# SDI_1521L_BREAKOUT_BOARD.net
KiCad netlist of a schematic drawn in Altium Designer
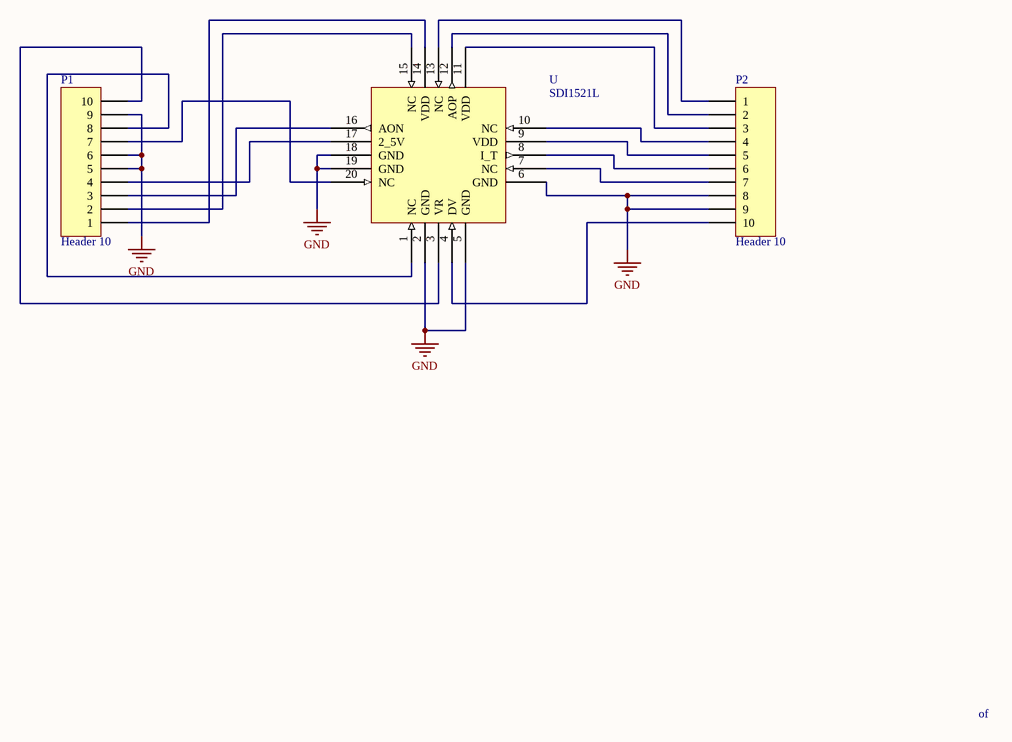
[diagram p0: SDI_1521L_BREAKOUT_BOARD.SchDoc]

(export (version "E")
  (design (tool "Eeschema 10.0.6"))
  (components
    (comp (ref "P1")
      (value "Header 10")
      (footprint "HDR1X10")
      (description "Header, 10-Pin")
      (fields (field (name "PUBLISHER") "Altium Limited"))
      (libsource (lib "") (part "Header 10_1"))
    )
    (comp (ref "P2")
      (value "Header 10")
      (footprint "HDR1X10")
      (description "Header, 10-Pin")
      (fields (field (name "PUBLISHER") "Altium Limited"))
      (libsource (lib "Miscellaneous Connectors") (part "Header 10"))
    )
    (comp (ref "U")
      (value "SDI1521L")
      (footprint "SDI 1521L")
      (description "SDI1521L Accelerometer +/- 2G")
      (libsource (lib "GAINS_SCH") (part "SDI1521L"))
    )
  )
  (nets
    (net (code "1") (name "GND") (class "Default")
      (node (ref "P1") (pin "5") (pinfunction "5_5") (pintype "passive"))
      (node (ref "P1") (pin "6") (pinfunction "6_6") (pintype "passive"))
      (node (ref "P1") (pin "9") (pinfunction "9_9") (pintype "passive"))
      (node (ref "P2") (pin "8") (pinfunction "8_8") (pintype "passive"))
      (node (ref "P2") (pin "9") (pinfunction "9_9") (pintype "passive"))
      (node (ref "U") (pin "18") (pinfunction "GND_18") (pintype "passive"))
      (node (ref "U") (pin "19") (pinfunction "GND_19") (pintype "passive"))
      (node (ref "U") (pin "2") (pinfunction "GND_2") (pintype "passive"))
      (node (ref "U") (pin "5") (pinfunction "GND_5") (pintype "passive"))
      (node (ref "U") (pin "6") (pinfunction "GND_6") (pintype "passive"))
    )
    (net (code "2") (name "Net-(P1-Pad1)") (class "Default")
      (node (ref "P1") (pin "1") (pinfunction "1_1") (pintype "passive"))
      (node (ref "U") (pin "14") (pinfunction "VDD_14") (pintype "passive"))
    )
    (net (code "3") (name "Net-(P1-Pad2)") (class "Default")
      (node (ref "P1") (pin "2") (pinfunction "2_2") (pintype "passive"))
      (node (ref "U") (pin "15") (pinfunction "NC_15") (pintype "input"))
    )
    (net (code "4") (name "Net-(P1-Pad7)") (class "Default")
      (node (ref "P1") (pin "7") (pinfunction "7_7") (pintype "passive"))
      (node (ref "U") (pin "20") (pinfunction "NC_20") (pintype "input"))
    )
    (net (code "5") (name "Net-(P1-Pad8)") (class "Default")
      (node (ref "P1") (pin "8") (pinfunction "8_8") (pintype "passive"))
      (node (ref "U") (pin "1") (pinfunction "NC_1") (pintype "input"))
    )
    (net (code "6") (name "Net-(P2-Pad1)") (class "Default")
      (node (ref "P2") (pin "1") (pinfunction "1_1") (pintype "passive"))
      (node (ref "U") (pin "13") (pinfunction "NC_13") (pintype "input"))
    )
    (net (code "7") (name "Net-(P2-Pad3)") (class "Default")
      (node (ref "P2") (pin "3") (pinfunction "3_3") (pintype "passive"))
      (node (ref "U") (pin "11") (pinfunction "VDD_11") (pintype "passive"))
    )
    (net (code "8") (name "Net-(P2-Pad4)") (class "Default")
      (node (ref "P2") (pin "4") (pinfunction "4_4") (pintype "passive"))
      (node (ref "U") (pin "10") (pinfunction "NC_10") (pintype "input"))
    )
    (net (code "9") (name "Net-(P2-Pad5)") (class "Default")
      (node (ref "P2") (pin "5") (pinfunction "5_5") (pintype "passive"))
      (node (ref "U") (pin "9") (pinfunction "VDD_9") (pintype "passive"))
    )
    (net (code "10") (name "Net-(P2-Pad7)") (class "Default")
      (node (ref "P2") (pin "7") (pinfunction "7_7") (pintype "passive"))
      (node (ref "U") (pin "7") (pinfunction "NC_7") (pintype "input"))
    )
    (net (code "11") (name "Net-(U-2_5V)") (class "Default")
      (node (ref "P1") (pin "4") (pinfunction "4_4") (pintype "passive"))
      (node (ref "U") (pin "17") (pinfunction "2_5V_17") (pintype "passive"))
    )
    (net (code "12") (name "Net-(U-AON)") (class "Default")
      (node (ref "P1") (pin "3") (pinfunction "3_3") (pintype "passive"))
      (node (ref "U") (pin "16") (pinfunction "AON_16") (pintype "output"))
    )
    (net (code "13") (name "Net-(U-AOP)") (class "Default")
      (node (ref "P2") (pin "2") (pinfunction "2_2") (pintype "passive"))
      (node (ref "U") (pin "12") (pinfunction "AOP_12") (pintype "output"))
    )
    (net (code "14") (name "Net-(U-DV)") (class "Default")
      (node (ref "P2") (pin "10") (pinfunction "10_10") (pintype "passive"))
      (node (ref "U") (pin "4") (pinfunction "DV_4") (pintype "input"))
    )
    (net (code "15") (name "Net-(U-I_T)") (class "Default")
      (node (ref "P2") (pin "6") (pinfunction "6_6") (pintype "passive"))
      (node (ref "U") (pin "8") (pinfunction "I_T_8") (pintype "output"))
    )
    (net (code "16") (name "Net-(U-VR)") (class "Default")
      (node (ref "P1") (pin "10") (pinfunction "10_10") (pintype "passive"))
      (node (ref "U") (pin "3") (pinfunction "VR_3") (pintype "passive"))
    )
  )
)
